# Apollo_3.net
KiCad netlist of a schematic drawn in Altium Designer
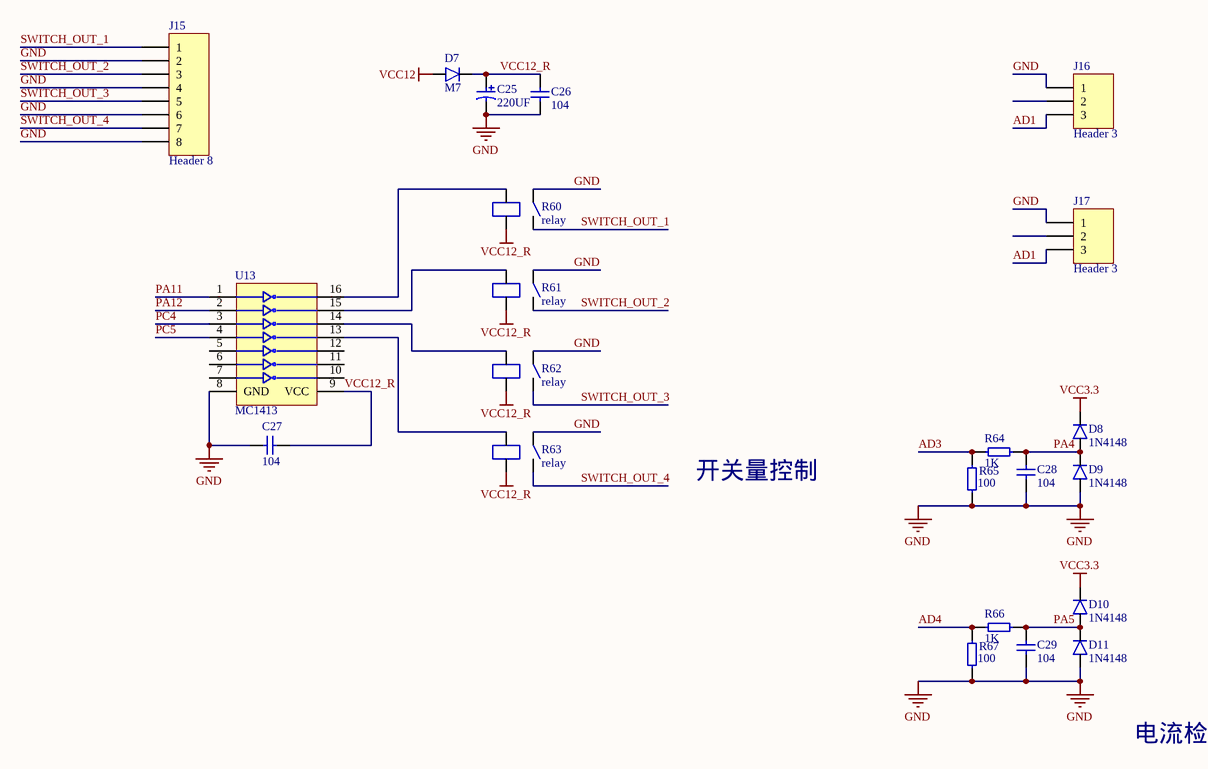
[diagram p0: Apollo_3.SchDoc]

(export (version "E")
  (design (tool "Eeschema 10.0.6"))
  (components
    (comp (ref "C25") (value "220UF") (footprint "RB 2.5/6.3") (libsource (lib "basic") (part "CAP-POL2")))
    (comp (ref "C26") (value "104") (footprint "0805C") (libsource (lib "basic") (part "CAP")))
    (comp (ref "C27") (value "104") (footprint "0805C") (libsource (lib "basic") (part "CAP")))
    (comp (ref "C28") (value "104") (footprint "0805C") (libsource (lib "basic") (part "CAP")))
    (comp (ref "C29") (value "104") (footprint "0805C") (libsource (lib "basic") (part "CAP")))
    (comp (ref "D7") (value "M7") (footprint "SMA (DO-214AC)") (libsource (lib "diodes") (part "M7")))
    (comp (ref "D8") (value "1N4148") (footprint "SOD 323") (libsource (lib "diodes") (part "1N4148")))
    (comp (ref "D9") (value "1N4148") (footprint "SOD 323") (libsource (lib "diodes") (part "1N4148")))
    (comp (ref "D10") (value "1N4148") (footprint "SOD 323") (libsource (lib "diodes") (part "1N4148")))
    (comp (ref "D11") (value "1N4148") (footprint "SOD 323") (libsource (lib "diodes") (part "1N4148")))
    (comp (ref "J15")
      (value "Header 8")
      (footprint "2EDG 8-3.80")
      (description "Header, 8-Pin")
      (fields (field (name "PUBLISHER") "Altium Limited"))
      (libsource (lib "Miscellaneous Connectors") (part "Header 8"))
    )
    (comp (ref "J16")
      (value "Header 3")
      (footprint "3EDG 3-5.08")
      (description "Header, 3-Pin")
      (fields (field (name "PUBLISHER") "Altium Limited"))
      (libsource (lib "Miscellaneous Connectors") (part "Header 3"))
    )
    (comp (ref "J17")
      (value "Header 3")
      (footprint "3EDG 3-3.80")
      (description "Header, 3-Pin")
      (fields (field (name "PUBLISHER") "Altium Limited"))
      (libsource (lib "Miscellaneous Connectors") (part "Header 3"))
    )
    (comp (ref "R60") (value "relay") (footprint "HF49FD/012-1H11") (libsource (lib "misc") (part "relay")))
    (comp (ref "R61") (value "relay") (footprint "HF49FD/012-1H11") (libsource (lib "misc") (part "relay")))
    (comp (ref "R62") (value "relay") (footprint "HF49FD/012-1H11") (libsource (lib "misc") (part "relay")))
    (comp (ref "R63") (value "relay") (footprint "HF49FD/012-1H11") (libsource (lib "misc") (part "relay")))
    (comp (ref "R64") (value "1K") (footprint "0805") (libsource (lib "basic") (part "RES")))
    (comp (ref "R65") (value "100") (footprint "0805") (libsource (lib "basic") (part "RES")))
    (comp (ref "R66") (value "1K") (footprint "0805") (libsource (lib "basic") (part "RES")))
    (comp (ref "R67") (value "100") (footprint "0805") (libsource (lib "basic") (part "RES")))
    (comp (ref "U13")
      (value "MC1413")
      (footprint "SOP 16-1.27/3.9")
      (libsource (lib "digital") (part "MC1413"))
    )
  )
  (nets
    (net (code "1") (name "/AD1") (class "Default")
      (node (ref "J16") (pin "3") (pinfunction "3_3") (pintype "passive"))
      (node (ref "J17") (pin "3") (pinfunction "3_3") (pintype "passive"))
    )
    (net (code "2") (name "/AD3") (class "Default")
      (node (ref "R64") (pin "2") (pinfunction "2_2") (pintype "passive"))
      (node (ref "R65") (pin "2") (pinfunction "2_2") (pintype "passive"))
    )
    (net (code "3") (name "/AD4") (class "Default")
      (node (ref "R66") (pin "2") (pinfunction "2_2") (pintype "passive"))
      (node (ref "R67") (pin "2") (pinfunction "2_2") (pintype "passive"))
    )
    (net (code "4") (name "/PA4") (class "Default")
      (node (ref "C28") (pin "2") (pinfunction "2_2") (pintype "passive"))
      (node (ref "D8") (pin "2") (pinfunction "+_2") (pintype "passive"))
      (node (ref "D9") (pin "1") (pinfunction "-_1") (pintype "passive"))
      (node (ref "R64") (pin "1") (pinfunction "1_1") (pintype "passive"))
    )
    (net (code "5") (name "/PA5") (class "Default")
      (node (ref "C29") (pin "2") (pinfunction "2_2") (pintype "passive"))
      (node (ref "D10") (pin "2") (pinfunction "+_2") (pintype "passive"))
      (node (ref "D11") (pin "1") (pinfunction "-_1") (pintype "passive"))
      (node (ref "R66") (pin "1") (pinfunction "1_1") (pintype "passive"))
    )
    (net (code "6") (name "/PA11") (class "Default")
      (node (ref "U13") (pin "1") (pinfunction "1_1") (pintype "passive"))
    )
    (net (code "7") (name "/PA12") (class "Default")
      (node (ref "U13") (pin "2") (pinfunction "2_2") (pintype "passive"))
    )
    (net (code "8") (name "/PC4") (class "Default")
      (node (ref "U13") (pin "3") (pinfunction "3_3") (pintype "passive"))
    )
    (net (code "9") (name "/PC5") (class "Default")
      (node (ref "U13") (pin "4") (pinfunction "4_4") (pintype "passive"))
    )
    (net (code "10") (name "/SWITCH_OUT_1") (class "Default")
      (node (ref "J15") (pin "1") (pinfunction "1_1") (pintype "passive"))
      (node (ref "R60") (pin "4") (pinfunction "4_4") (pintype "passive"))
    )
    (net (code "11") (name "/SWITCH_OUT_2") (class "Default")
      (node (ref "J15") (pin "3") (pinfunction "3_3") (pintype "passive"))
      (node (ref "R61") (pin "4") (pinfunction "4_4") (pintype "passive"))
    )
    (net (code "12") (name "/SWITCH_OUT_3") (class "Default")
      (node (ref "J15") (pin "5") (pinfunction "5_5") (pintype "passive"))
      (node (ref "R62") (pin "4") (pinfunction "4_4") (pintype "passive"))
    )
    (net (code "13") (name "/SWITCH_OUT_4") (class "Default")
      (node (ref "J15") (pin "7") (pinfunction "7_7") (pintype "passive"))
      (node (ref "R63") (pin "4") (pinfunction "4_4") (pintype "passive"))
    )
    (net (code "16") (name "GND") (class "Default")
      (node (ref "C25") (pin "1") (pinfunction "1_1") (pintype "passive"))
      (node (ref "C26") (pin "1") (pinfunction "1_1") (pintype "passive"))
      (node (ref "C27") (pin "1") (pinfunction "1_1") (pintype "passive"))
      (node (ref "C28") (pin "1") (pinfunction "1_1") (pintype "passive"))
      (node (ref "C29") (pin "1") (pinfunction "1_1") (pintype "passive"))
      (node (ref "D11") (pin "2") (pinfunction "+_2") (pintype "passive"))
      (node (ref "D9") (pin "2") (pinfunction "+_2") (pintype "passive"))
      (node (ref "J15") (pin "2") (pinfunction "2_2") (pintype "passive"))
      (node (ref "J15") (pin "4") (pinfunction "4_4") (pintype "passive"))
      (node (ref "J15") (pin "6") (pinfunction "6_6") (pintype "passive"))
      (node (ref "J15") (pin "8") (pinfunction "8_8") (pintype "passive"))
      (node (ref "J16") (pin "1") (pinfunction "1_1") (pintype "passive"))
      (node (ref "J17") (pin "1") (pinfunction "1_1") (pintype "passive"))
      (node (ref "R60") (pin "3") (pinfunction "3_3") (pintype "passive"))
      (node (ref "R61") (pin "3") (pinfunction "3_3") (pintype "passive"))
      (node (ref "R62") (pin "3") (pinfunction "3_3") (pintype "passive"))
      (node (ref "R63") (pin "3") (pinfunction "3_3") (pintype "passive"))
      (node (ref "R65") (pin "1") (pinfunction "1_1") (pintype "passive"))
      (node (ref "R67") (pin "1") (pinfunction "1_1") (pintype "passive"))
      (node (ref "U13") (pin "8") (pinfunction "GND_8") (pintype "passive"))
    )
    (net (code "17") (name "Net-(R60-Pad1)") (class "Default")
      (node (ref "R60") (pin "1") (pinfunction "1_1") (pintype "passive"))
      (node (ref "U13") (pin "16") (pinfunction "16_16") (pintype "passive"))
    )
    (net (code "18") (name "Net-(R61-Pad1)") (class "Default")
      (node (ref "R61") (pin "1") (pinfunction "1_1") (pintype "passive"))
      (node (ref "U13") (pin "15") (pinfunction "15_15") (pintype "passive"))
    )
    (net (code "19") (name "Net-(R62-Pad1)") (class "Default")
      (node (ref "R62") (pin "1") (pinfunction "1_1") (pintype "passive"))
      (node (ref "U13") (pin "14") (pinfunction "14_14") (pintype "passive"))
    )
    (net (code "20") (name "Net-(R63-Pad1)") (class "Default")
      (node (ref "R63") (pin "1") (pinfunction "1_1") (pintype "passive"))
      (node (ref "U13") (pin "13") (pinfunction "13_13") (pintype "passive"))
    )
    (net (code "21") (name "VCC3.3") (class "Default")
      (node (ref "D10") (pin "1") (pinfunction "-_1") (pintype "passive"))
      (node (ref "D8") (pin "1") (pinfunction "-_1") (pintype "passive"))
    )
    (net (code "22") (name "VCC12") (class "Default")
      (node (ref "D7") (pin "2") (pinfunction "+_2") (pintype "passive"))
    )
    (net (code "23") (name "VCC12_R") (class "Default")
      (node (ref "C25") (pin "2") (pinfunction "2_2") (pintype "passive"))
      (node (ref "C26") (pin "2") (pinfunction "2_2") (pintype "passive"))
      (node (ref "C27") (pin "2") (pinfunction "2_2") (pintype "passive"))
      (node (ref "D7") (pin "1") (pinfunction "-_1") (pintype "passive"))
      (node (ref "R60") (pin "2") (pinfunction "2_2") (pintype "passive"))
      (node (ref "R61") (pin "2") (pinfunction "2_2") (pintype "passive"))
      (node (ref "R62") (pin "2") (pinfunction "2_2") (pintype "passive"))
      (node (ref "R63") (pin "2") (pinfunction "2_2") (pintype "passive"))
      (node (ref "U13") (pin "9") (pinfunction "VCC_9") (pintype "passive"))
    )
    (net (code "24") (name "unconnected-(J16-Pad2)") (class "Default")
      (node (ref "J16") (pin "2") (pinfunction "2_2") (pintype "passive"))
    )
    (net (code "25") (name "unconnected-(J17-Pad2)") (class "Default")
      (node (ref "J17") (pin "2") (pinfunction "2_2") (pintype "passive"))
    )
    (net (code "26") (name "unconnected-(U13-Pad5)") (class "Default")
      (node (ref "U13") (pin "5") (pinfunction "5_5") (pintype "passive"))
    )
    (net (code "27") (name "unconnected-(U13-Pad6)") (class "Default")
      (node (ref "U13") (pin "6") (pinfunction "6_6") (pintype "passive"))
    )
    (net (code "28") (name "unconnected-(U13-Pad7)") (class "Default")
      (node (ref "U13") (pin "7") (pinfunction "7_7") (pintype "passive"))
    )
    (net (code "29") (name "unconnected-(U13-Pad10)") (class "Default")
      (node (ref "U13") (pin "10") (pinfunction "10_10") (pintype "passive"))
    )
    (net (code "30") (name "unconnected-(U13-Pad11)") (class "Default")
      (node (ref "U13") (pin "11") (pinfunction "11_11") (pintype "passive"))
    )
    (net (code "31") (name "unconnected-(U13-Pad12)") (class "Default")
      (node (ref "U13") (pin "12") (pinfunction "12_12") (pintype "passive"))
    )
  )
)
